# easyeda.net
KiCad netlist of a schematic drawn in EasyEDA
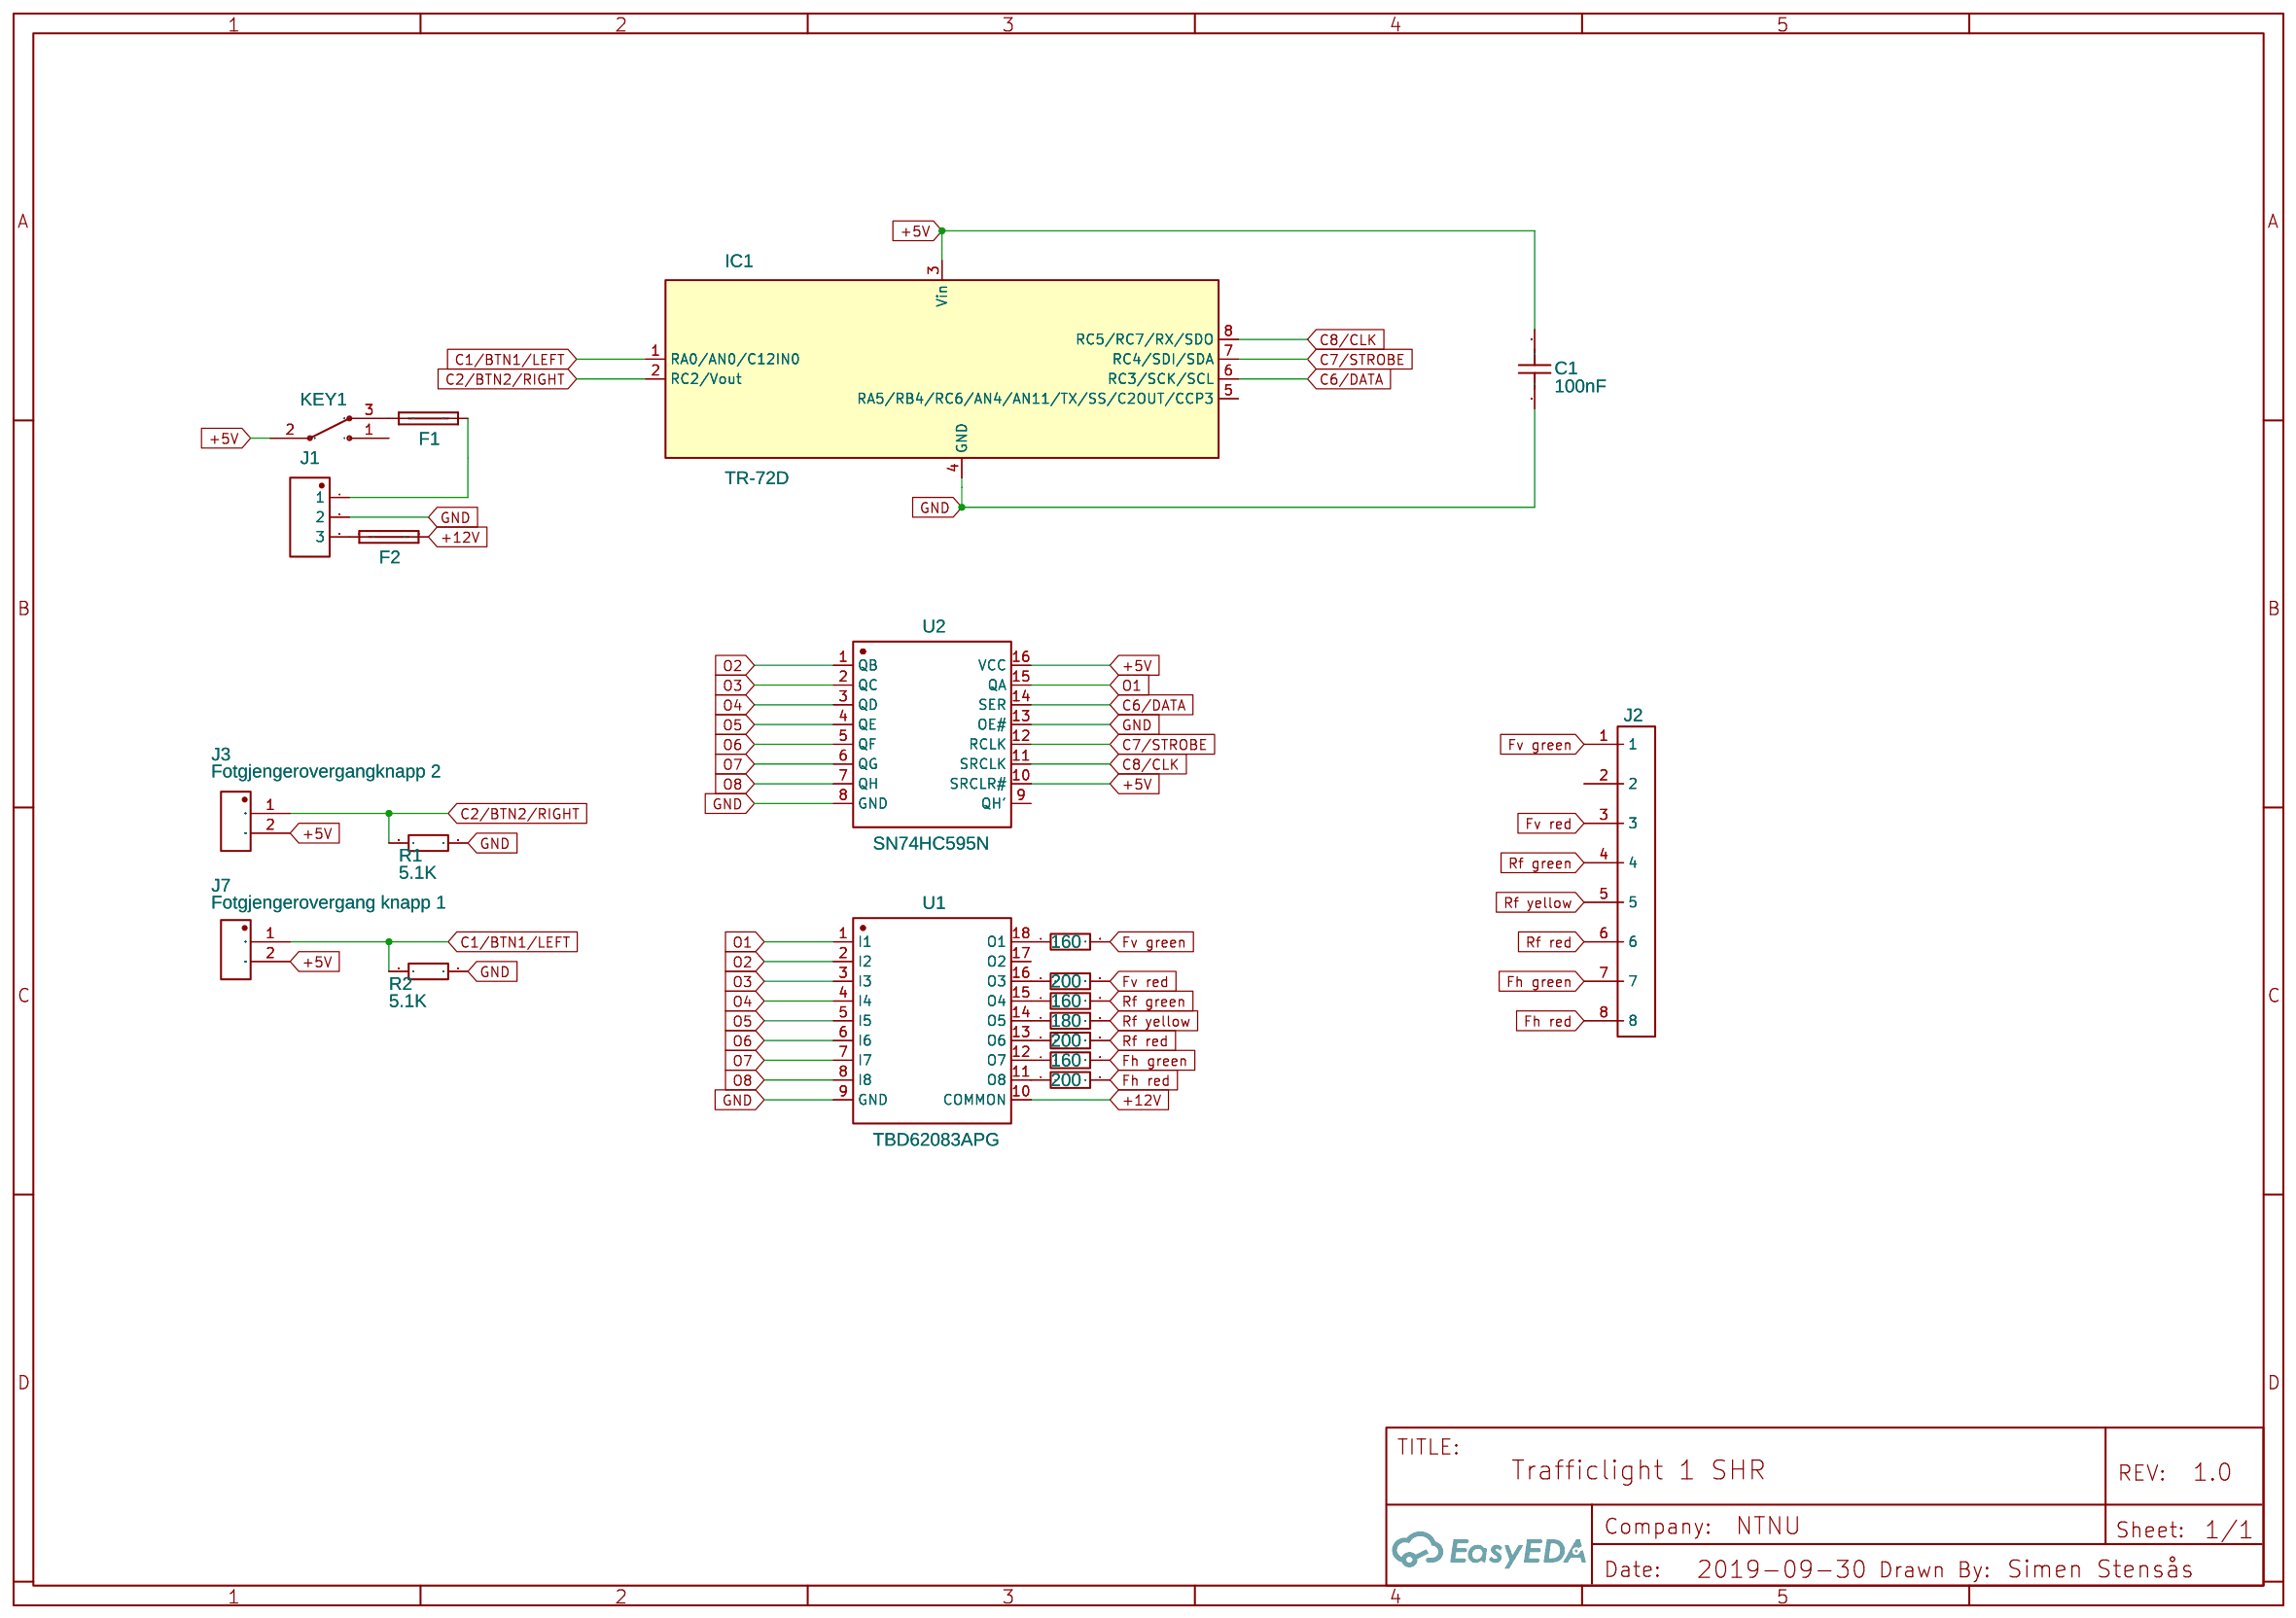
[diagram p0: schematic sheet]

(export (version "E")
  (design (tool "Eeschema 10.0.6"))
  (components
    (comp (ref "C1")
      (value "100nF")
      (fields
        (field (name "BOM_Manufacturer Part") "1210B106K100CT")
        (field (name "BOM_Supplier Part") "C304011")
      )
      (libsource (lib "") (part "1210B106K100CT"))
    )
    (comp (ref "F1")
      (value "NO")
      (fields
        (field (name "BOM_Manufacturer Part") "3403.0015.11")
        (field (name "BOM_Supplier Part") "693-3403.0015.11")
      )
      (libsource (lib "") (part "Unknown_215_195"))
    )
    (comp (ref "F2")
      (value "NO")
      (fields
        (field (name "BOM_Manufacturer Part") "3403.0015.11")
        (field (name "BOM_Supplier Part") "693-3403.0015.11")
      )
      (libsource (lib "") (part "Unknown_195_255"))
    )
    (comp (ref "IC1") (value "TR-72D") (libsource (lib "") (part "Unknown_330_175")))
    (comp (ref "J1") (value "KF127_3P_5.08") (libsource (lib "") (part "Unknown_150_255")))
    (comp (ref "J2") (value "KF127-8P") (libsource (lib "") (part "Unknown_815_430")))
    (comp (ref "J3")
      (value "Fotgjengerovergangknapp 2")
      (fields (field (name "BOM_Manufacturer Part") "KF127L-5.08"))
      (libsource (lib "") (part "Unknown_125_410"))
    )
    (comp (ref "J7")
      (value "Fotgjengerovergang knapp 1")
      (fields (field (name "BOM_Manufacturer Part") "KF127L-5.08"))
      (libsource (lib "") (part "Unknown_125_475"))
    )
    (comp (ref "KEY1")
      (value "MSK-11027 Toggle Switches")
      (fields (field (name "BOM_Supplier Part") "C21381"))
      (libsource (lib "") (part "Unknown_160_205"))
    )
    (comp (ref "R1")
      (value "5.1K")
      (fields
        (field (name "BOM_Manufacturer Part") "RMC12065.1K1%N")
        (field (name "BOM_Supplier Part") "C325932")
      )
      (libsource (lib "") (part "RMC12065.1K1%N"))
    )
    (comp (ref "R2")
      (value "5.1K")
      (fields
        (field (name "BOM_Manufacturer Part") "RMC12065.1K1%N")
        (field (name "BOM_Supplier Part") "C325932")
      )
      (libsource (lib "") (part "RMC12065.1K1%N"))
    )
    (comp (ref "R8")
      (value "160")
      (fields
        (field (name "BOM_Manufacturer Part") "RC1206JR-07160RL")
        (field (name "BOM_Supplier Part") "C137196")
      )
      (libsource (lib "") (part "RC1206JR-07160RL"))
    )
    (comp (ref "R9")
      (value "160")
      (fields
        (field (name "BOM_Manufacturer Part") "RC1206JR-07160RL")
        (field (name "BOM_Supplier Part") "C137196")
      )
      (libsource (lib "") (part "RC1206JR-07160RL"))
    )
    (comp (ref "R10")
      (value "160")
      (fields
        (field (name "BOM_Manufacturer Part") "RC1206JR-07160RL")
        (field (name "BOM_Supplier Part") "C137196")
      )
      (libsource (lib "") (part "RC1206JR-07160RL"))
    )
    (comp (ref "R12")
      (value "180")
      (fields
        (field (name "BOM_Manufacturer Part") "CR1206-FX-1800ELF")
        (field (name "BOM_Supplier Part") "C204708")
      )
      (libsource (lib "") (part "CR1206-FX-1800ELF"))
    )
    (comp (ref "R13")
      (value "200")
      (fields
        (field (name "BOM_Manufacturer Part") "QR1206J200RP05")
        (field (name "BOM_Supplier Part") "C149886")
      )
      (libsource (lib "") (part "QR1206J200RP05"))
    )
    (comp (ref "R14")
      (value "200")
      (fields
        (field (name "BOM_Manufacturer Part") "QR1206J200RP05")
        (field (name "BOM_Supplier Part") "C149886")
      )
      (libsource (lib "") (part "QR1206J200RP05"))
    )
    (comp (ref "R15")
      (value "200")
      (fields
        (field (name "BOM_Manufacturer Part") "QR1206J200RP05")
        (field (name "BOM_Supplier Part") "C149886")
      )
      (libsource (lib "") (part "QR1206J200RP05"))
    )
    (comp (ref "U1")
      (value "TBD62083APG")
      (fields (field (name "BOM_Supplier Part") "C114143"))
      (libsource (lib "") (part "Unknown_465_510"))
    )
    (comp (ref "U2")
      (value "SN74HC595N")
      (fields (field (name "BOM_Supplier Part") "C78711"))
      (libsource (lib "") (part "Unknown_465_365"))
    )
  )
  (nets
    (net (code "1") (name "+5V") (class "Default")
      (node (ref "C1") (pin "2") (pinfunction "2_2") (pintype "unspecified"))
      (node (ref "IC1") (pin "3") (pinfunction "Vin_3") (pintype "bidirectional"))
      (node (ref "J3") (pin "2") (pinfunction "PIN2_2") (pintype "unspecified"))
      (node (ref "J7") (pin "2") (pinfunction "PIN2_2") (pintype "unspecified"))
      (node (ref "KEY1") (pin "2") (pinfunction "2_2") (pintype "unspecified"))
      (node (ref "U2") (pin "10") (pinfunction "SRCLR#_10") (pintype "unspecified"))
      (node (ref "U2") (pin "16") (pinfunction "VCC_16") (pintype "unspecified"))
    )
    (net (code "2") (name "+12V") (class "Default")
      (node (ref "F2") (pin "2") (pinfunction "2_2") (pintype "bidirectional"))
      (node (ref "U1") (pin "10") (pinfunction "COMMON_10") (pintype "unspecified"))
    )
    (net (code "3") (name "C1{slash}BTN1{slash}LEFT") (class "Default")
      (node (ref "IC1") (pin "1") (pinfunction "RA0/AN0/C12IN0_1") (pintype "bidirectional"))
      (node (ref "J7") (pin "1") (pinfunction "PIN1_1") (pintype "unspecified"))
      (node (ref "R2") (pin "1") (pinfunction "1_1") (pintype "unspecified"))
    )
    (net (code "4") (name "C2{slash}BTN2{slash}RIGHT") (class "Default")
      (node (ref "IC1") (pin "2") (pinfunction "RC2/Vout_2") (pintype "bidirectional"))
      (node (ref "J3") (pin "1") (pinfunction "PIN1_1") (pintype "unspecified"))
      (node (ref "R1") (pin "1") (pinfunction "1_1") (pintype "unspecified"))
    )
    (net (code "5") (name "C6{slash}DATA") (class "Default")
      (node (ref "IC1") (pin "6") (pinfunction "RC3/SCK/SCL_6") (pintype "bidirectional"))
      (node (ref "U2") (pin "14") (pinfunction "SER_14") (pintype "unspecified"))
    )
    (net (code "6") (name "C7{slash}STROBE") (class "Default")
      (node (ref "IC1") (pin "7") (pinfunction "RC4/SDI/SDA_7") (pintype "bidirectional"))
      (node (ref "U2") (pin "12") (pinfunction "RCLK_12") (pintype "unspecified"))
    )
    (net (code "7") (name "C8{slash}CLK") (class "Default")
      (node (ref "IC1") (pin "8") (pinfunction "RC5/RC7/RX/SDO_8") (pintype "bidirectional"))
      (node (ref "U2") (pin "11") (pinfunction "SRCLK_11") (pintype "unspecified"))
    )
    (net (code "8") (name "Fh green") (class "Default")
      (node (ref "J2") (pin "7") (pinfunction "7_7") (pintype "unspecified"))
      (node (ref "R10") (pin "2") (pinfunction "2_2") (pintype "input"))
    )
    (net (code "9") (name "Fh red") (class "Default")
      (node (ref "J2") (pin "8") (pinfunction "8_8") (pintype "unspecified"))
      (node (ref "R15") (pin "2") (pinfunction "2_2") (pintype "unspecified"))
    )
    (net (code "10") (name "Fv green") (class "Default")
      (node (ref "J2") (pin "1") (pinfunction "1_1") (pintype "unspecified"))
      (node (ref "R8") (pin "2") (pinfunction "2_2") (pintype "input"))
    )
    (net (code "11") (name "Fv red") (class "Default")
      (node (ref "J2") (pin "3") (pinfunction "3_3") (pintype "unspecified"))
      (node (ref "R13") (pin "2") (pinfunction "2_2") (pintype "unspecified"))
    )
    (net (code "12") (name "GND") (class "Default")
      (node (ref "C1") (pin "1") (pinfunction "1_1") (pintype "unspecified"))
      (node (ref "IC1") (pin "4") (pinfunction "GND_4") (pintype "bidirectional"))
      (node (ref "J1") (pin "2") (pinfunction "2_2") (pintype "input"))
      (node (ref "R1") (pin "2") (pinfunction "2_2") (pintype "unspecified"))
      (node (ref "R2") (pin "2") (pinfunction "2_2") (pintype "unspecified"))
      (node (ref "U1") (pin "9") (pinfunction "GND_9") (pintype "unspecified"))
      (node (ref "U2") (pin "13") (pinfunction "OE#_13") (pintype "unspecified"))
      (node (ref "U2") (pin "8") (pinfunction "GND_8") (pintype "unspecified"))
    )
    (net (code "13") (name "Net-(F1-Pad1)") (class "Default")
      (node (ref "F1") (pin "1") (pinfunction "1_1") (pintype "bidirectional"))
      (node (ref "KEY1") (pin "3") (pinfunction "3_3") (pintype "unspecified"))
    )
    (net (code "14") (name "Net-(F1-Pad2)") (class "Default")
      (node (ref "F1") (pin "2") (pinfunction "2_2") (pintype "bidirectional"))
      (node (ref "J1") (pin "1") (pinfunction "1_1") (pintype "input"))
    )
    (net (code "15") (name "Net-(F2-Pad1)") (class "Default")
      (node (ref "F2") (pin "1") (pinfunction "1_1") (pintype "bidirectional"))
      (node (ref "J1") (pin "3") (pinfunction "3_3") (pintype "input"))
    )
    (net (code "16") (name "Net-(U1-O1)") (class "Default")
      (node (ref "R8") (pin "1") (pinfunction "1_1") (pintype "input"))
      (node (ref "U1") (pin "18") (pinfunction "O1_18") (pintype "unspecified"))
    )
    (net (code "17") (name "Net-(U1-O3)") (class "Default")
      (node (ref "R13") (pin "1") (pinfunction "1_1") (pintype "unspecified"))
      (node (ref "U1") (pin "16") (pinfunction "O3_16") (pintype "unspecified"))
    )
    (net (code "18") (name "Net-(U1-O4)") (class "Default")
      (node (ref "R9") (pin "1") (pinfunction "1_1") (pintype "input"))
      (node (ref "U1") (pin "15") (pinfunction "O4_15") (pintype "unspecified"))
    )
    (net (code "19") (name "Net-(U1-O5)") (class "Default")
      (node (ref "R12") (pin "1") (pinfunction "1_1") (pintype "unspecified"))
      (node (ref "U1") (pin "14") (pinfunction "O5_14") (pintype "unspecified"))
    )
    (net (code "20") (name "Net-(U1-O6)") (class "Default")
      (node (ref "R14") (pin "1") (pinfunction "1_1") (pintype "unspecified"))
      (node (ref "U1") (pin "13") (pinfunction "O6_13") (pintype "unspecified"))
    )
    (net (code "21") (name "Net-(U1-O7)") (class "Default")
      (node (ref "R10") (pin "1") (pinfunction "1_1") (pintype "input"))
      (node (ref "U1") (pin "12") (pinfunction "O7_12") (pintype "unspecified"))
    )
    (net (code "22") (name "Net-(U1-O8)") (class "Default")
      (node (ref "R15") (pin "1") (pinfunction "1_1") (pintype "unspecified"))
      (node (ref "U1") (pin "11") (pinfunction "O8_11") (pintype "unspecified"))
    )
    (net (code "23") (name "O1") (class "Default")
      (node (ref "U1") (pin "1") (pinfunction "I1_1") (pintype "unspecified"))
      (node (ref "U2") (pin "15") (pinfunction "QA_15") (pintype "unspecified"))
    )
    (net (code "24") (name "O2") (class "Default")
      (node (ref "U1") (pin "2") (pinfunction "I2_2") (pintype "unspecified"))
      (node (ref "U2") (pin "1") (pinfunction "QB_1") (pintype "unspecified"))
    )
    (net (code "25") (name "O3") (class "Default")
      (node (ref "U1") (pin "3") (pinfunction "I3_3") (pintype "unspecified"))
      (node (ref "U2") (pin "2") (pinfunction "QC_2") (pintype "unspecified"))
    )
    (net (code "26") (name "O4") (class "Default")
      (node (ref "U1") (pin "4") (pinfunction "I4_4") (pintype "unspecified"))
      (node (ref "U2") (pin "3") (pinfunction "QD_3") (pintype "unspecified"))
    )
    (net (code "27") (name "O5") (class "Default")
      (node (ref "U1") (pin "5") (pinfunction "I5_5") (pintype "unspecified"))
      (node (ref "U2") (pin "4") (pinfunction "QE_4") (pintype "unspecified"))
    )
    (net (code "28") (name "O6") (class "Default")
      (node (ref "U1") (pin "6") (pinfunction "I6_6") (pintype "unspecified"))
      (node (ref "U2") (pin "5") (pinfunction "QF_5") (pintype "unspecified"))
    )
    (net (code "29") (name "O7") (class "Default")
      (node (ref "U1") (pin "7") (pinfunction "I7_7") (pintype "unspecified"))
      (node (ref "U2") (pin "6") (pinfunction "QG_6") (pintype "unspecified"))
    )
    (net (code "30") (name "O8") (class "Default")
      (node (ref "U1") (pin "8") (pinfunction "I8_8") (pintype "unspecified"))
      (node (ref "U2") (pin "7") (pinfunction "QH_7") (pintype "unspecified"))
    )
    (net (code "31") (name "Rf green") (class "Default")
      (node (ref "J2") (pin "4") (pinfunction "4_4") (pintype "unspecified"))
      (node (ref "R9") (pin "2") (pinfunction "2_2") (pintype "input"))
    )
    (net (code "32") (name "Rf red") (class "Default")
      (node (ref "J2") (pin "6") (pinfunction "6_6") (pintype "unspecified"))
      (node (ref "R14") (pin "2") (pinfunction "2_2") (pintype "unspecified"))
    )
    (net (code "33") (name "Rf yellow") (class "Default")
      (node (ref "J2") (pin "5") (pinfunction "5_5") (pintype "unspecified"))
      (node (ref "R12") (pin "2") (pinfunction "2_2") (pintype "unspecified"))
    )
    (net (code "34") (name "unconnected-(IC1-RA5{slash}RB4{slash}RC6{slash}AN4{slash}AN11{slash}TX{slash}SS{slash}C2OUT{slash}CCP3-Pad5)") (class "Default")
      (node (ref "IC1") (pin "5") (pinfunction "RA5/RB4/RC6/AN4/AN11/TX/SS/C2OUT/CCP3_5") (pintype "bidirectional"))
    )
    (net (code "35") (name "unconnected-(J2-Pad2)") (class "Default")
      (node (ref "J2") (pin "2") (pinfunction "2_2") (pintype "unspecified"))
    )
    (net (code "36") (name "unconnected-(KEY1-Pad1)") (class "Default")
      (node (ref "KEY1") (pin "1") (pinfunction "1_1") (pintype "unspecified"))
    )
    (net (code "37") (name "unconnected-(U1-O2-Pad17)") (class "Default")
      (node (ref "U1") (pin "17") (pinfunction "O2_17") (pintype "unspecified"))
    )
    (net (code "38") (name "unconnected-(U2-QH'-Pad9)") (class "Default")
      (node (ref "U2") (pin "9") (pinfunction "QH'_9") (pintype "unspecified"))
    )
  )
)
